# roulette_wheel.net
KiCad netlist of a schematic drawn in EAGLE
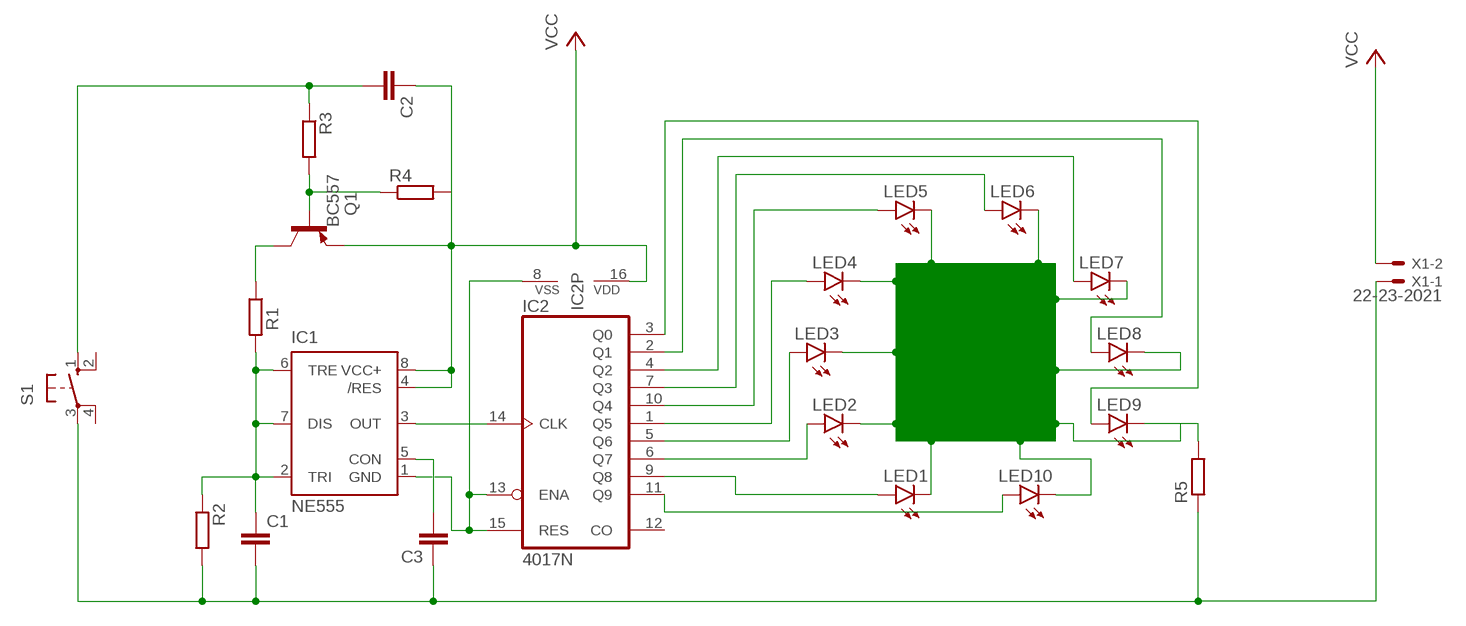
[diagram p0: schematic, sheet 1]

(export (version "E")
  (design (tool "Eeschema 10.0.6"))
  (components
    (comp (ref "C1")
      (value "C-EU025-024X044")
      (footprint "eagle-import:C025-024X044")
      (libsource (lib "eagle-import") (part "C-EU025-024X044"))
    )
    (comp (ref "C2")
      (value "C-EU025-024X044")
      (footprint "eagle-import:C025-024X044")
      (libsource (lib "eagle-import") (part "C-EU025-024X044"))
    )
    (comp (ref "C3")
      (value "C-EU025-024X044")
      (footprint "eagle-import:C025-024X044")
      (libsource (lib "eagle-import") (part "C-EU025-024X044"))
    )
    (comp (ref "IC1")
      (value "NE555")
      (footprint "eagle-import:DIL-08")
      (fields (field (name "MF") "Arrow Electronics") (field (name "MPN") "NE555N"))
      (libsource (lib "eagle-import") (part "NE555"))
    )
    (comp (ref "IC2")
      (value "4017N")
      (footprint "eagle-import:DIL16")
      (libsource (lib "eagle-import") (part "4017N"))
    )
    (comp (ref "LED1")
      (value "LED3MM")
      (footprint "eagle-import:LED3MM")
      (libsource (lib "eagle-import") (part "LED3MM"))
    )
    (comp (ref "LED2")
      (value "LED3MM")
      (footprint "eagle-import:LED3MM")
      (libsource (lib "eagle-import") (part "LED3MM"))
    )
    (comp (ref "LED3")
      (value "LED3MM")
      (footprint "eagle-import:LED3MM")
      (libsource (lib "eagle-import") (part "LED3MM"))
    )
    (comp (ref "LED4")
      (value "LED3MM")
      (footprint "eagle-import:LED3MM")
      (libsource (lib "eagle-import") (part "LED3MM"))
    )
    (comp (ref "LED5")
      (value "LED3MM")
      (footprint "eagle-import:LED3MM")
      (libsource (lib "eagle-import") (part "LED3MM"))
    )
    (comp (ref "LED6")
      (value "LED3MM")
      (footprint "eagle-import:LED3MM")
      (libsource (lib "eagle-import") (part "LED3MM"))
    )
    (comp (ref "LED7")
      (value "LED3MM")
      (footprint "eagle-import:LED3MM")
      (libsource (lib "eagle-import") (part "LED3MM"))
    )
    (comp (ref "LED8")
      (value "LED3MM")
      (footprint "eagle-import:LED3MM")
      (libsource (lib "eagle-import") (part "LED3MM"))
    )
    (comp (ref "LED9")
      (value "LED3MM")
      (footprint "eagle-import:LED3MM")
      (libsource (lib "eagle-import") (part "LED3MM"))
    )
    (comp (ref "LED10")
      (value "LED3MM")
      (footprint "eagle-import:LED3MM")
      (libsource (lib "eagle-import") (part "LED3MM"))
    )
    (comp (ref "Q1")
      (value "BC557")
      (footprint "eagle-import:TO92")
      (libsource (lib "eagle-import") (part "BC557"))
    )
    (comp (ref "R1")
      (value "R-EU_0204/7")
      (footprint "eagle-import:0204_7")
      (libsource (lib "eagle-import") (part "R-EU_0204/7"))
    )
    (comp (ref "R2")
      (value "R-EU_0204/7")
      (footprint "eagle-import:0204_7")
      (libsource (lib "eagle-import") (part "R-EU_0204/7"))
    )
    (comp (ref "R3")
      (value "R-EU_0204/7")
      (footprint "eagle-import:0204_7")
      (libsource (lib "eagle-import") (part "R-EU_0204/7"))
    )
    (comp (ref "R4")
      (value "R-EU_0204/7")
      (footprint "eagle-import:0204_7")
      (libsource (lib "eagle-import") (part "R-EU_0204/7"))
    )
    (comp (ref "R5")
      (value "R-EU_0204/7")
      (footprint "eagle-import:0204_7")
      (libsource (lib "eagle-import") (part "R-EU_0204/7"))
    )
    (comp (ref "S1")
      (value "10-XX")
      (footprint "eagle-import:B3F-10XX")
      (fields (field (name "MPN") "B3F-1000"))
      (libsource (lib "eagle-import") (part "10-XX"))
    )
    (comp (ref "X1")
      (value "22-23-2021")
      (footprint "eagle-import:22-23-2021")
      (fields (field (name "MF") "MOLEX"))
      (libsource (lib "eagle-import") (part "22-23-2021"))
    )
  )
  (nets
    (net (code "1") (name "Net-(IC1-CON)") (class "Default")
      (node (ref "C3") (pin "2") (pinfunction "2_2") (pintype "passive"))
      (node (ref "IC1") (pin "5") (pinfunction "CON_5") (pintype "input"))
    )
    (net (code "2") (name "Net-(IC1-DIS)") (class "Default")
      (node (ref "C1") (pin "1") (pinfunction "1_1") (pintype "passive"))
      (node (ref "IC1") (pin "2") (pinfunction "TRI_2") (pintype "input"))
      (node (ref "IC1") (pin "6") (pinfunction "TRE_6") (pintype "input"))
      (node (ref "IC1") (pin "7") (pinfunction "DIS_7") (pintype "input"))
      (node (ref "R1") (pin "2") (pinfunction "2_2") (pintype "passive"))
      (node (ref "R2") (pin "1") (pinfunction "1_1") (pintype "passive"))
    )
    (net (code "3") (name "Net-(IC1-OUT)") (class "Default")
      (node (ref "IC1") (pin "3") (pinfunction "OUT_3") (pintype "output"))
      (node (ref "IC2") (pin "14") (pinfunction "CLK_14") (pintype "input"))
    )
    (net (code "4") (name "Net-(IC2A-ENA)") (class "Default")
      (node (ref "IC2") (pin "13") (pinfunction "ENA_13") (pintype "input"))
      (node (ref "IC2") (pin "15") (pinfunction "RES_15") (pintype "input"))
      (node (ref "IC2") (pin "8") (pinfunction "VSS_8") (pintype "power_in"))
    )
    (net (code "5") (name "Net-(IC2A-Q0)") (class "Default")
      (node (ref "IC2") (pin "3") (pinfunction "Q0_3") (pintype "output"))
      (node (ref "LED9") (pin "A") (pinfunction "A_A") (pintype "passive"))
    )
    (net (code "6") (name "Net-(IC2A-Q1)") (class "Default")
      (node (ref "IC2") (pin "2") (pinfunction "Q1_2") (pintype "output"))
      (node (ref "LED8") (pin "A") (pinfunction "A_A") (pintype "passive"))
    )
    (net (code "7") (name "Net-(IC2A-Q2)") (class "Default")
      (node (ref "IC2") (pin "4") (pinfunction "Q2_4") (pintype "output"))
      (node (ref "LED7") (pin "A") (pinfunction "A_A") (pintype "passive"))
    )
    (net (code "8") (name "Net-(IC2A-Q3)") (class "Default")
      (node (ref "IC2") (pin "7") (pinfunction "Q3_7") (pintype "output"))
      (node (ref "LED6") (pin "A") (pinfunction "A_A") (pintype "passive"))
    )
    (net (code "9") (name "Net-(IC2A-Q4)") (class "Default")
      (node (ref "IC2") (pin "10") (pinfunction "Q4_10") (pintype "output"))
      (node (ref "LED5") (pin "A") (pinfunction "A_A") (pintype "passive"))
    )
    (net (code "10") (name "Net-(IC2A-Q5)") (class "Default")
      (node (ref "IC2") (pin "1") (pinfunction "Q5_1") (pintype "output"))
      (node (ref "LED4") (pin "A") (pinfunction "A_A") (pintype "passive"))
    )
    (net (code "11") (name "Net-(IC2A-Q6)") (class "Default")
      (node (ref "IC2") (pin "5") (pinfunction "Q6_5") (pintype "output"))
      (node (ref "LED3") (pin "A") (pinfunction "A_A") (pintype "passive"))
    )
    (net (code "12") (name "Net-(IC2A-Q7)") (class "Default")
      (node (ref "IC2") (pin "6") (pinfunction "Q7_6") (pintype "output"))
      (node (ref "LED2") (pin "A") (pinfunction "A_A") (pintype "passive"))
    )
    (net (code "13") (name "Net-(IC2A-Q8)") (class "Default")
      (node (ref "IC2") (pin "9") (pinfunction "Q8_9") (pintype "output"))
      (node (ref "LED1") (pin "A") (pinfunction "A_A") (pintype "passive"))
    )
    (net (code "14") (name "Net-(IC2A-Q9)") (class "Default")
      (node (ref "IC2") (pin "11") (pinfunction "Q9_11") (pintype "output"))
      (node (ref "LED10") (pin "A") (pinfunction "A_A") (pintype "passive"))
    )
    (net (code "15") (name "Net-(LED9-C)") (class "Default")
      (node (ref "LED9") (pin "K") (pinfunction "C_K") (pintype "passive"))
      (node (ref "R5") (pin "2") (pinfunction "2_2") (pintype "passive"))
    )
    (net (code "16") (name "Net-(Q1-B)") (class "Default")
      (node (ref "Q1") (pin "2") (pinfunction "B_2") (pintype "passive"))
      (node (ref "R3") (pin "2") (pinfunction "2_2") (pintype "passive"))
      (node (ref "R4") (pin "1") (pinfunction "1_1") (pintype "passive"))
    )
    (net (code "17") (name "Net-(Q1-C)") (class "Default")
      (node (ref "Q1") (pin "3") (pinfunction "C_3") (pintype "passive"))
      (node (ref "R1") (pin "1") (pinfunction "1_1") (pintype "passive"))
    )
    (net (code "18") (name "Net-(S1-P)") (class "Default")
      (node (ref "C1") (pin "2") (pinfunction "2_2") (pintype "passive"))
      (node (ref "C3") (pin "1") (pinfunction "1_1") (pintype "passive"))
      (node (ref "R2") (pin "2") (pinfunction "2_2") (pintype "passive"))
      (node (ref "R5") (pin "1") (pinfunction "1_1") (pintype "passive"))
      (node (ref "S1") (pin "3") (pinfunction "P_3") (pintype "passive"))
      (node (ref "X1") (pin "1") (pinfunction "S_1") (pintype "passive"))
    )
    (net (code "19") (name "Net-(S1-S)") (class "Default")
      (node (ref "C2") (pin "2") (pinfunction "2_2") (pintype "passive"))
      (node (ref "R3") (pin "1") (pinfunction "1_1") (pintype "passive"))
      (node (ref "S1") (pin "1") (pinfunction "S_1") (pintype "passive"))
    )
    (net (code "20") (name "VCC") (class "Default")
      (node (ref "C2") (pin "1") (pinfunction "1_1") (pintype "passive"))
      (node (ref "IC1") (pin "4") (pinfunction "/RES_4") (pintype "input"))
      (node (ref "IC1") (pin "8") (pinfunction "VCC+_8") (pintype "power_in"))
      (node (ref "IC2") (pin "16") (pinfunction "VDD_16") (pintype "power_in"))
      (node (ref "Q1") (pin "1") (pinfunction "E_1") (pintype "passive"))
      (node (ref "R4") (pin "2") (pinfunction "2_2") (pintype "passive"))
      (node (ref "X1") (pin "2") (pinfunction "S_2") (pintype "passive"))
    )
    (net (code "21") (name "unconnected-(IC1-GND-Pad1)") (class "Default")
      (node (ref "IC1") (pin "1") (pinfunction "GND_1") (pintype "power_in"))
    )
    (net (code "22") (name "unconnected-(IC2A-CO-Pad12)") (class "Default")
      (node (ref "IC2") (pin "12") (pinfunction "CO_12") (pintype "output"))
    )
    (net (code "23") (name "unconnected-(LED1-C-PadK)") (class "Default")
      (node (ref "LED1") (pin "K") (pinfunction "C_K") (pintype "passive"))
    )
    (net (code "24") (name "unconnected-(LED2-C-PadK)") (class "Default")
      (node (ref "LED2") (pin "K") (pinfunction "C_K") (pintype "passive"))
    )
    (net (code "25") (name "unconnected-(LED3-C-PadK)") (class "Default")
      (node (ref "LED3") (pin "K") (pinfunction "C_K") (pintype "passive"))
    )
    (net (code "26") (name "unconnected-(LED4-C-PadK)") (class "Default")
      (node (ref "LED4") (pin "K") (pinfunction "C_K") (pintype "passive"))
    )
    (net (code "27") (name "unconnected-(LED5-C-PadK)") (class "Default")
      (node (ref "LED5") (pin "K") (pinfunction "C_K") (pintype "passive"))
    )
    (net (code "28") (name "unconnected-(LED6-C-PadK)") (class "Default")
      (node (ref "LED6") (pin "K") (pinfunction "C_K") (pintype "passive"))
    )
    (net (code "29") (name "unconnected-(LED7-C-PadK)") (class "Default")
      (node (ref "LED7") (pin "K") (pinfunction "C_K") (pintype "passive"))
    )
    (net (code "30") (name "unconnected-(LED8-C-PadK)") (class "Default")
      (node (ref "LED8") (pin "K") (pinfunction "C_K") (pintype "passive"))
    )
    (net (code "31") (name "unconnected-(LED10-C-PadK)") (class "Default")
      (node (ref "LED10") (pin "K") (pinfunction "C_K") (pintype "passive"))
    )
    (net (code "32") (name "unconnected-(S1-P1-Pad4)") (class "Default")
      (node (ref "S1") (pin "4") (pinfunction "P1_4") (pintype "passive"))
    )
    (net (code "33") (name "unconnected-(S1-S1-Pad2)") (class "Default")
      (node (ref "S1") (pin "2") (pinfunction "S1_2") (pintype "passive"))
    )
  )
)
